# EVQ4242-VE-00B_schematic.net
KiCad netlist of a schematic drawn in Altium Designer
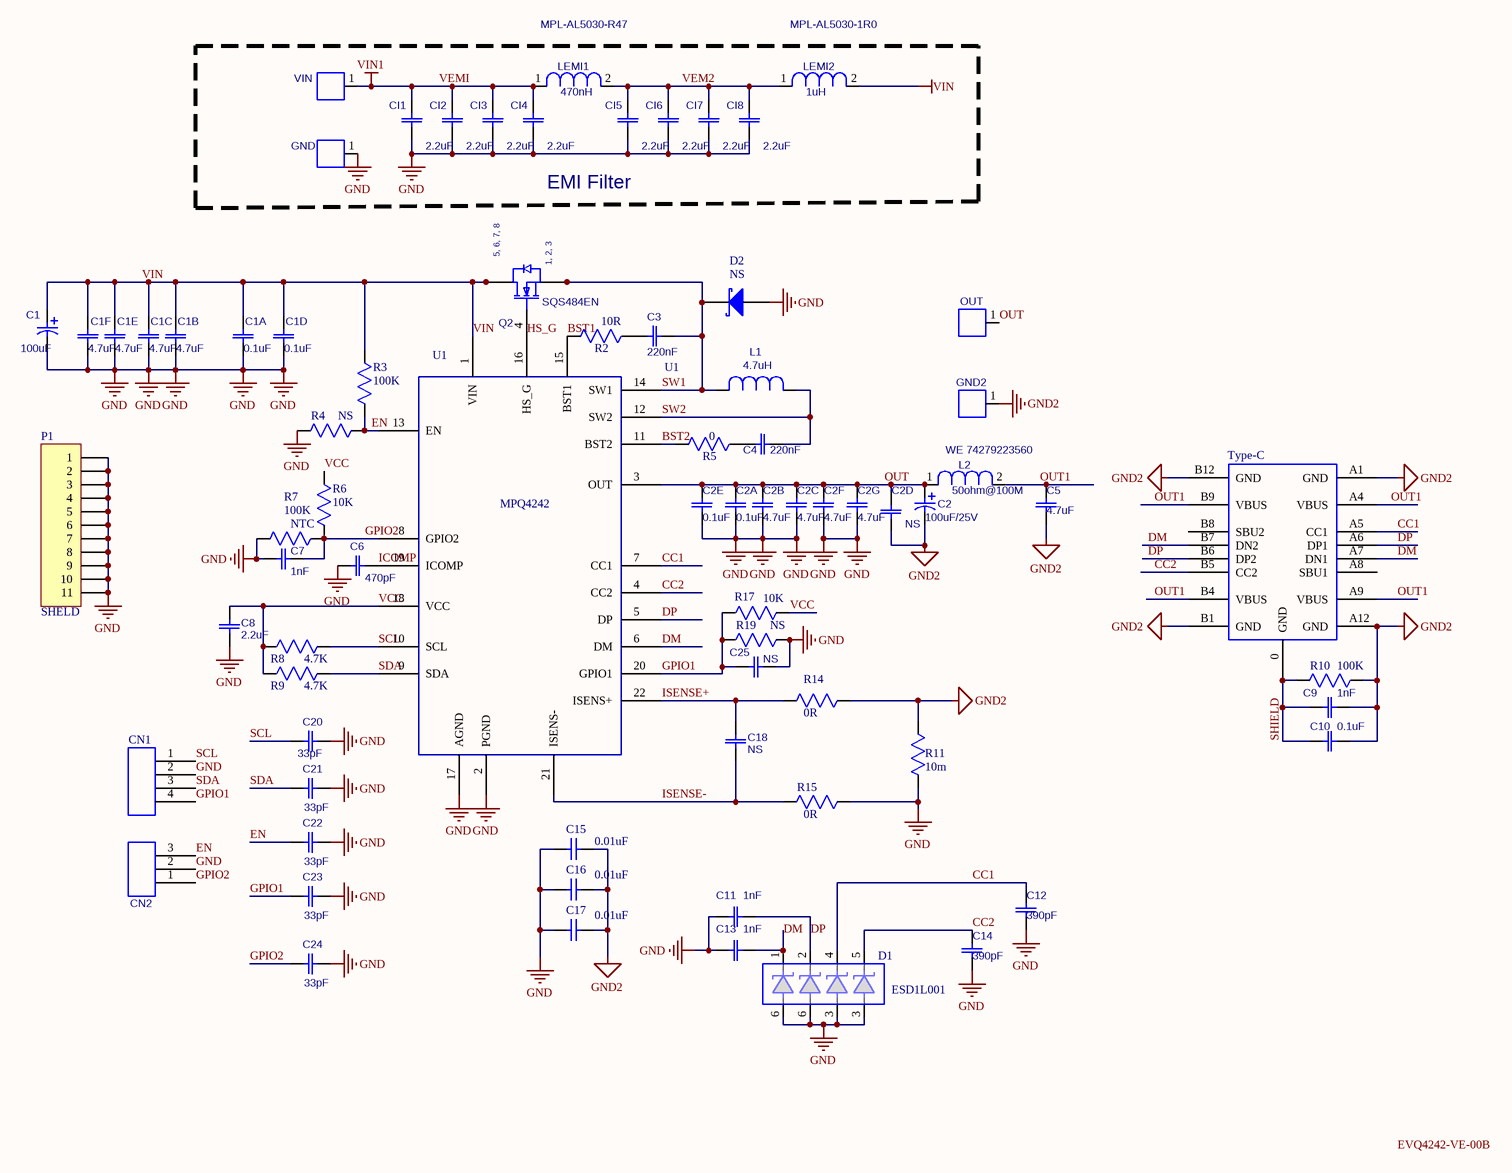
[diagram p0: EVQ4242-VE-00B_schematic.SchDoc]

(export (version "E")
  (design (tool "Eeschema 10.0.6"))
  (components
    (comp (ref "C1")
      (value "100uF")
      (footprint "CAP/ELECT/SMD/C6")
      (description "Electrolytic Capacitor;50V;Electrolytic;DIP")
      (fields (field (name "MANUFACTURER") "{Manufacturer}") (field (name "PART NUMBER") "07.0271"))
      (libsource (lib "MPSLab") (part "CAP/ELECT/DIP/OD5.3P2.0"))
    )
    (comp (ref "C1A")
      (value "0.1uF")
      (footprint "CAP/0402")
      (description "{Description}")
      (fields (field (name "MANUFACTURER") "{Manufacturer}"))
      (libsource (lib "*") (part "CAP0603"))
    )
    (comp (ref "C1B")
      (value "4.7uF")
      (footprint "CAP/0805")
      (description "{Description}")
      (fields (field (name "MANUFACTURER") "{Manufacturer}"))
      (libsource (lib "*") (part "CAP0603"))
    )
    (comp (ref "C1C")
      (value "4.7uF")
      (footprint "CAP/0805")
      (description "Ceramic Cap., 50V, X7R")
      (fields (field (name "MANUFACTURER") "TDK"))
      (libsource (lib "*") (part "CAP1210"))
    )
    (comp (ref "C1D")
      (value "0.1uF")
      (footprint "CAP/0402")
      (description "{Description}")
      (fields (field (name "MANUFACTURER") "{Manufacturer}"))
      (libsource (lib "*") (part "CAP0603"))
    )
    (comp (ref "C1E")
      (value "4.7uF")
      (footprint "CAP/0805")
      (description "{Description}")
      (fields (field (name "MANUFACTURER") "{Manufacturer}"))
      (libsource (lib "*") (part "CAP0603"))
    )
    (comp (ref "C1F")
      (value "4.7uF")
      (footprint "CAP/0805")
      (description "Ceramic Cap., 50V, X7R")
      (fields (field (name "MANUFACTURER") "TDK"))
      (libsource (lib "*") (part "CAP1210"))
    )
    (comp (ref "C2")
      (value "100uF/25V")
      (footprint "6.6mm*6.6mm")
      (description "Electrolytic Capacitor;50V;Electrolytic;DIP")
      (fields (field (name "MANUFACTURER") "{Manufacturer}") (field (name "PART NUMBER") "07.0271"))
      (libsource (lib "MPSLab") (part "CAP/ELECT/DIP/OD5.3P2.0"))
    )
    (comp (ref "C2A")
      (value "0.1uF")
      (footprint "CAP/0402")
      (description "{Description}")
      (fields (field (name "MANUFACTURER") "{Manufacturer}"))
      (libsource (lib "*") (part "CAP0603"))
    )
    (comp (ref "C2B")
      (value "4.7uF")
      (footprint "CAP/0805")
      (description "{Description}")
      (fields (field (name "MANUFACTURER") "{Manufacturer}"))
      (libsource (lib "*") (part "CAP0603"))
    )
    (comp (ref "C2C")
      (value "4.7uF")
      (footprint "CAP/0805")
      (description "{Description}")
      (fields (field (name "MANUFACTURER") "{Manufacturer}"))
      (libsource (lib "*") (part "CAP0603"))
    )
    (comp (ref "C2D")
      (value "NS")
      (footprint "CAP/0805")
      (description "{Description}")
      (fields (field (name "MANUFACTURER") "{Manufacturer}"))
      (libsource (lib "*") (part "CAP0603"))
    )
    (comp (ref "C2E")
      (value "0.1uF")
      (footprint "CAP/0402")
      (description "{Description}")
      (fields (field (name "MANUFACTURER") "{Manufacturer}"))
      (libsource (lib "*") (part "CAP0603"))
    )
    (comp (ref "C2F")
      (value "4.7uF")
      (footprint "CAP/0805")
      (description "{Description}")
      (fields (field (name "MANUFACTURER") "{Manufacturer}"))
      (libsource (lib "*") (part "CAP0603"))
    )
    (comp (ref "C2G")
      (value "4.7uF")
      (footprint "CAP/0805")
      (description "{Description}")
      (fields (field (name "MANUFACTURER") "{Manufacturer}"))
      (libsource (lib "*") (part "CAP0603"))
    )
    (comp (ref "C3")
      (value "220nF")
      (footprint "CAP/0402")
      (description "{Description}")
      (fields (field (name "MANUFACTURER") "{Manufacturer}"))
      (libsource (lib "*") (part "CAP0603"))
    )
    (comp (ref "C4")
      (value "220nF")
      (footprint "CAP/0402")
      (description "{Description}")
      (fields (field (name "MANUFACTURER") "{Manufacturer}"))
      (libsource (lib "*") (part "CAP0603"))
    )
    (comp (ref "C5")
      (value "4.7uF")
      (footprint "CAP/0603")
      (description "{Description}")
      (fields (field (name "MANUFACTURER") "{Manufacturer}"))
      (libsource (lib "*") (part "CAP0603"))
    )
    (comp (ref "C6")
      (value "470pF")
      (footprint "CAP/0402")
      (description "{Description}")
      (fields (field (name "MANUFACTURER") "{Manufacturer}"))
      (libsource (lib "*") (part "CAP0603"))
    )
    (comp (ref "C7")
      (value "1nF")
      (footprint "CAP/0603")
      (description "{Description}")
      (fields (field (name "MANUFACTURER") "{Manufacturer}"))
      (libsource (lib "*") (part "CAP0603"))
    )
    (comp (ref "C8")
      (value "2.2uF")
      (footprint "CAP/0402")
      (description "{Description}")
      (fields (field (name "MANUFACTURER") "{Manufacturer}"))
      (libsource (lib "*") (part "CAP0603"))
    )
    (comp (ref "C9")
      (value "1nF")
      (footprint "CAP/0603")
      (description "Ceramic Cap.,50V,X7R")
      (fields (field (name "MANUFACTURER") "WE") (field (name "Comment") "CA~{P}0603"))
      (libsource (lib "*") (part "CAP0603"))
    )
    (comp (ref "C10")
      (value "0.1uF")
      (footprint "CAP/0603")
      (description "Ceramic Cap.,50V,X7R")
      (fields (field (name "MANUFACTURER") "WE") (field (name "Comment") "CA~{P}0603"))
      (libsource (lib "*") (part "CAP0603"))
    )
    (comp (ref "C11")
      (value "1nF")
      (footprint "CAP/0402")
      (description "Ceramic Cap.,50V,C0G")
      (fields (field (name "MANUFACTURER") "Murata") (field (name "Comment") "CA~{P}0603"))
      (libsource (lib "*") (part "CAP0603"))
    )
    (comp (ref "C12")
      (value "390pF")
      (footprint "CAP/0402")
      (description "{Description}")
      (fields (field (name "MANUFACTURER") "{Manufacturer}"))
      (libsource (lib "*") (part "CAP0603"))
    )
    (comp (ref "C13")
      (value "1nF")
      (footprint "CAP/0402")
      (description "Ceramic Cap.,50V,C0G")
      (fields (field (name "MANUFACTURER") "Murata") (field (name "Comment") "CA~{P}0603"))
      (libsource (lib "*") (part "CAP0603"))
    )
    (comp (ref "C14")
      (value "390pF")
      (footprint "CAP/0402")
      (description "{Description}")
      (fields (field (name "MANUFACTURER") "{Manufacturer}"))
      (libsource (lib "*") (part "CAP0603"))
    )
    (comp (ref "C15")
      (value "0.01uF")
      (footprint "CAP/0402")
      (description "Capacitor")
      (fields (field (name "MANUFACTURER") "muRata") (field (name "Comment") "Cap"))
      (libsource (lib "SMCAP") (part "Cap"))
    )
    (comp (ref "C16")
      (value "0.01uF")
      (footprint "CAP/0402")
      (description "Capacitor")
      (fields (field (name "MANUFACTURER") "muRata") (field (name "Comment") "Cap"))
      (libsource (lib "SMCAP") (part "Cap"))
    )
    (comp (ref "C17")
      (value "0.01uF")
      (footprint "CAP/0402")
      (description "Capacitor")
      (fields (field (name "MANUFACTURER") "muRata") (field (name "Comment") "Cap"))
      (libsource (lib "SMCAP") (part "Cap"))
    )
    (comp (ref "C18")
      (value "NS")
      (footprint "CAP/0402")
      (description "{Description}")
      (fields (field (name "MANUFACTURER") "{Manufacturer}"))
      (libsource (lib "*") (part "CAP0603"))
    )
    (comp (ref "C20")
      (value "33pF")
      (footprint "CAP0603")
      (description "{Description}")
      (fields (field (name "MANUFACTURER") "{Manufacturer}"))
      (libsource (lib "MPS_CAPACITOR") (part "CAP0402"))
    )
    (comp (ref "C21")
      (value "33pF")
      (footprint "CAP0603")
      (description "{Description}")
      (fields (field (name "MANUFACTURER") "{Manufacturer}"))
      (libsource (lib "MPS_CAPACITOR") (part "CAP0402"))
    )
    (comp (ref "C22")
      (value "33pF")
      (footprint "CAP0603")
      (description "{Description}")
      (fields (field (name "MANUFACTURER") "{Manufacturer}"))
      (libsource (lib "MPS_CAPACITOR") (part "CAP0402"))
    )
    (comp (ref "C23")
      (value "33pF")
      (footprint "CAP0603")
      (description "{Description}")
      (fields (field (name "MANUFACTURER") "{Manufacturer}"))
      (libsource (lib "MPS_CAPACITOR") (part "CAP0402"))
    )
    (comp (ref "C24")
      (value "33pF")
      (footprint "CAP0603")
      (description "{Description}")
      (fields (field (name "MANUFACTURER") "{Manufacturer}"))
      (libsource (lib "MPS_CAPACITOR") (part "CAP0402"))
    )
    (comp (ref "C25")
      (value "NS")
      (footprint "CAP/0603")
      (description "{Description}")
      (fields (field (name "MANUFACTURER") "{Manufacturer}"))
      (libsource (lib "*") (part "CAP0603"))
    )
    (comp (ref "CI1")
      (value "2.2uF")
      (footprint "CAP0603")
      (description "{Description}")
      (fields (field (name "MANUFACTURER") "{Manufacturer}") (field (name "Comment") "CAP0603"))
      (libsource (lib "MPS_CAPACITOR") (part "CAP0603"))
    )
    (comp (ref "CI2")
      (value "2.2uF")
      (footprint "CAP0603")
      (description "{Description}")
      (fields (field (name "MANUFACTURER") "{Manufacturer}") (field (name "Comment") "CAP0603"))
      (libsource (lib "MPS_CAPACITOR") (part "CAP0603"))
    )
    (comp (ref "CI3")
      (value "2.2uF")
      (footprint "CAP0603")
      (description "{Description}")
      (fields (field (name "MANUFACTURER") "{Manufacturer}") (field (name "Comment") "CAP0603"))
      (libsource (lib "MPS_CAPACITOR") (part "CAP0603"))
    )
    (comp (ref "CI4")
      (value "2.2uF")
      (footprint "CAP0603")
      (description "{Description}")
      (fields (field (name "MANUFACTURER") "{Manufacturer}") (field (name "Comment") "CAP0603"))
      (libsource (lib "MPS_CAPACITOR") (part "CAP0603"))
    )
    (comp (ref "CI5")
      (value "2.2uF")
      (footprint "CAP0603")
      (description "{Description}")
      (fields (field (name "MANUFACTURER") "{Manufacturer}") (field (name "Comment") "CAP0603"))
      (libsource (lib "MPS_CAPACITOR") (part "CAP0603"))
    )
    (comp (ref "CI6")
      (value "2.2uF")
      (footprint "CAP0603")
      (description "{Description}")
      (fields (field (name "MANUFACTURER") "{Manufacturer}") (field (name "Comment") "CAP0603"))
      (libsource (lib "MPS_CAPACITOR") (part "CAP0603"))
    )
    (comp (ref "CI7")
      (value "2.2uF")
      (footprint "CAP0603")
      (description "{Description}")
      (fields (field (name "MANUFACTURER") "{Manufacturer}") (field (name "Comment") "CAP0603"))
      (libsource (lib "MPS_CAPACITOR") (part "CAP0603"))
    )
    (comp (ref "CI8")
      (value "2.2uF")
      (footprint "CAP0603")
      (description "{Description}")
      (fields (field (name "MANUFACTURER") "{Manufacturer}") (field (name "Comment") "CAP0603"))
      (libsource (lib "MPS_CAPACITOR") (part "CAP0603"))
    )
    (comp (ref "CN1")
      (value "HEADER 4")
      (footprint "HEADER 1X4")
      (libsource (lib "T-EV5101-VE-00A") (part "HEADER 4"))
    )
    (comp (ref "CN2") (value "AC") (footprint "CONN/3PIN/2.54MM") (libsource (lib "Connector") (part "AC")))
    (comp (ref "D1")
      (value "ESD1L001")
      (footprint "ESD0001")
      (description "ESD Diode")
      (fields (field (name "MANUFACTURER") "Onsemi"))
      (libsource (lib "T-EVQ5031-4272-RE-00A") (part "ESD1L001"))
    )
    (comp (ref "D2")
      (value "NS")
      (footprint "SOD123")
      (description "Schottky Diode")
      (libsource (lib "Development kit-5M1270ZT144C5_1") (part "D Schottky"))
    )
    (comp (ref "GND")
      (value "CONN/1MM")
      (footprint "TP/2MM")
      (description "{Description}")
      (libsource (lib "Connector") (part "CONN/2MM"))
    )
    (comp (ref "GND2")
      (value "CONN/TP")
      (footprint "TP/2MM")
      (description "{Description}")
      (fields (field (name "MANUFACTURER") "{Manufacturer}"))
      (libsource (lib "Connector") (part "CONN/TP"))
    )
    (comp (ref "L1")
      (value "4.7uH")
      (footprint "7443551470")
      (description "{Description}")
      (fields (field (name "MANUFACTURER") "{Manufacturer}"))
      (libsource (lib "*") (part "TOKO106C"))
    )
    (comp (ref "L2")
      (value "50ohm@100M")
      (footprint "sm1206")
      (description "{Description}")
      (fields
        (field (name "PACKAGE") "WE 74279223560")
        (field (name "MANUFACTURER") "{Manufacturer}")
        (field (name "Comment") "L-10X10")
      )
      (libsource (lib "Inductor") (part "L-10X10"))
    )
    (comp (ref "LEMI1")
      (value "470nH")
      (footprint "L5030")
      (description "Inductor, 1.45A, D62LCB")
      (fields
        (field (name "PACKAGE") "MPL-AL5030-R47")
        (field (name "MANUFACTURER") "Toko")
        (field (name "Comment") "TDK-2520")
      )
      (libsource (lib "MPS_INDUCTOR") (part "TDK-2520"))
    )
    (comp (ref "LEMI2")
      (value "1uH")
      (footprint "L5030")
      (description "Inductor, 1.45A, D62LCB")
      (fields
        (field (name "MANUFACTURER") "Toko")
        (field (name "MANUFACTURER P/N") "MPL-AL5030-1R0")
        (field (name "Comment") "TDK-2520")
      )
      (libsource (lib "MPS_INDUCTOR") (part "TDK-2520"))
    )
    (comp (ref "OUT")
      (value "CONN/TP")
      (footprint "TP/2MM")
      (description "{Description}")
      (fields (field (name "MANUFACTURER") "{Manufacturer}"))
      (libsource (lib "Connector") (part "CONN/TP"))
    )
    (comp (ref "P1")
      (value "SHELD")
      (footprint "sheld")
      (libsource (lib "T-EVQ4242-VE-00A_1") (part "SHELD"))
    )
    (comp (ref "Q2")
      (value "SQS484EN")
      (footprint "SQS484EN")
      (description "AM4392N")
      (fields (field (name "ALTIUM_VALUE") "U1"))
      (libsource (lib "MOSFET") (part "AM4392N"))
    )
    (comp (ref "R2")
      (value "10R")
      (footprint "RES0402")
      (fields (field (name "Comment") "RES/DIP/1/2W"))
      (libsource (lib "Resistor") (part "RES/DIP/1/2W"))
    )
    (comp (ref "R3")
      (value "100K")
      (footprint "RES0603")
      (fields (field (name "Comment") "RES/DIP/1/2W"))
      (libsource (lib "Resistor") (part "RES/DIP/1/2W"))
    )
    (comp (ref "R4")
      (value "NS")
      (footprint "RES0603")
      (fields (field (name "Comment") "RES/DIP/1/2W"))
      (libsource (lib "Resistor") (part "RES/DIP/1/2W"))
    )
    (comp (ref "R5")
      (value "0")
      (footprint "RES0402")
      (fields (field (name "Comment") "RES/DIP/1/2W"))
      (libsource (lib "Resistor") (part "RES/DIP/1/2W"))
    )
    (comp (ref "R6")
      (value "10K")
      (footprint "RES0603")
      (fields (field (name "Comment") "RES/DIP/1/2W"))
      (libsource (lib "Resistor") (part "RES/DIP/1/2W"))
    )
    (comp (ref "R7")
      (value "NTC")
      (footprint "RES0603")
      (fields (field (name "ALTIUM_UNNAMED_1") "100K") (field (name "Comment") "RES/DIP/1/2W"))
      (libsource (lib "Resistor") (part "RES/DIP/1/2W"))
    )
    (comp (ref "R8")
      (value "4.7K")
      (footprint "RES0603")
      (fields (field (name "Comment") "RES/DIP/1/2W"))
      (libsource (lib "Resistor") (part "RES/DIP/1/2W"))
    )
    (comp (ref "R9")
      (value "4.7K")
      (footprint "RES0603")
      (fields (field (name "Comment") "RES/DIP/1/2W"))
      (libsource (lib "Resistor") (part "RES/DIP/1/2W"))
    )
    (comp (ref "R10")
      (value "100K")
      (footprint "RES0603")
      (fields (field (name "Comment") "RES/DIP/1/2W"))
      (libsource (lib "Resistor") (part "RES/DIP/1/2W"))
    )
    (comp (ref "R11")
      (value "10m")
      (footprint "l1508")
      (fields (field (name "Comment") "RES/DIP/1/2W"))
      (libsource (lib "Resistor") (part "RES/DIP/1/2W"))
    )
    (comp (ref "R14")
      (value "0R")
      (footprint "RES0402")
      (fields (field (name "Comment") "RES/DIP/1/2W"))
      (libsource (lib "Resistor") (part "RES/DIP/1/2W"))
    )
    (comp (ref "R15")
      (value "0R")
      (footprint "RES0402")
      (fields (field (name "Comment") "RES/DIP/1/2W"))
      (libsource (lib "Resistor") (part "RES/DIP/1/2W"))
    )
    (comp (ref "R17")
      (value "10K")
      (footprint "RES0603")
      (fields (field (name "Comment") "RES/DIP/1/2W"))
      (libsource (lib "Resistor") (part "RES/DIP/1/2W"))
    )
    (comp (ref "R19")
      (value "NS")
      (footprint "RES0603")
      (fields (field (name "Comment") "RES/DIP/1/2W"))
      (libsource (lib "Resistor") (part "RES/DIP/1/2W"))
    )
    (comp (ref "Type-C")
      (value "New Type_c")
      (footprint "New Type-C")
      (libsource (lib "BI-EVQ4252-QV-00A") (part "New Type_c"))
    )
    (comp (ref "U1")
      (value "MPQ4242")
      (footprint "QFN-22 (4mm×5mm)")
      (description "Buck-boost converter")
      (libsource (lib "T-EVQ4242-VE-00A") (part "QFN-22 (4MM*5MM)"))
    )
    (comp (ref "VIN")
      (value "CONN/2MM")
      (footprint "TP/2MM")
      (description "{Description}")
      (libsource (lib "Connector") (part "CONN/2MM"))
    )
  )
  (nets
    (net (code "1") (name "/BST1") (class "Default")
      (node (ref "R2") (pin "1") (pintype "passive"))
      (node (ref "U1") (pin "15") (pinfunction "BST1_15") (pintype "power_in"))
    )
    (net (code "2") (name "/BST2") (class "Default")
      (node (ref "R5") (pin "1") (pintype "passive"))
      (node (ref "U1") (pin "11") (pinfunction "BST2_11") (pintype "power_in"))
    )
    (net (code "3") (name "/CC1") (class "Default")
      (node (ref "C12") (pin "1") (pintype "passive"))
      (node (ref "D1") (pin "4") (pintype "passive"))
      (node (ref "Type-C") (pin "A5") (pinfunction "CC1_A5") (pintype "passive"))
      (node (ref "U1") (pin "7") (pinfunction "CC1_7") (pintype "power_in"))
    )
    (net (code "4") (name "/CC2") (class "Default")
      (node (ref "C14") (pin "1") (pintype "passive"))
      (node (ref "D1") (pin "5") (pintype "passive"))
      (node (ref "Type-C") (pin "B5") (pinfunction "CC2_B5") (pintype "passive"))
      (node (ref "U1") (pin "4") (pinfunction "CC2_4") (pintype "power_in"))
    )
    (net (code "5") (name "/DM") (class "Default")
      (node (ref "C13") (pin "2") (pintype "passive"))
      (node (ref "D1") (pin "1") (pintype "passive"))
      (node (ref "Type-C") (pin "A7") (pinfunction "DN1_A7") (pintype "passive"))
      (node (ref "Type-C") (pin "B7") (pinfunction "DN2_B7") (pintype "passive"))
      (node (ref "U1") (pin "6") (pinfunction "DM_6") (pintype "power_in"))
    )
    (net (code "6") (name "/DP") (class "Default")
      (node (ref "C11") (pin "2") (pintype "passive"))
      (node (ref "D1") (pin "2") (pintype "passive"))
      (node (ref "Type-C") (pin "A6") (pinfunction "DP1_A6") (pintype "passive"))
      (node (ref "Type-C") (pin "B6") (pinfunction "DP2_B6") (pintype "passive"))
      (node (ref "U1") (pin "5") (pinfunction "DP_5") (pintype "power_in"))
    )
    (net (code "7") (name "/EN") (class "Default")
      (node (ref "C22") (pin "2") (pintype "passive"))
      (node (ref "CN2") (pin "3") (pintype "passive"))
      (node (ref "R3") (pin "1") (pintype "passive"))
      (node (ref "R4") (pin "1") (pintype "passive"))
      (node (ref "U1") (pin "13") (pinfunction "EN_13") (pintype "power_in"))
    )
    (net (code "9") (name "/GPIO1") (class "Default")
      (node (ref "C23") (pin "2") (pintype "passive"))
      (node (ref "C25") (pin "1") (pintype "passive"))
      (node (ref "CN1") (pin "4") (pintype "passive"))
      (node (ref "R17") (pin "1") (pintype "passive"))
      (node (ref "R19") (pin "1") (pintype "passive"))
      (node (ref "U1") (pin "20") (pinfunction "GPIO1_20") (pintype "power_in"))
    )
    (net (code "10") (name "/GPIO2") (class "Default")
      (node (ref "C24") (pin "2") (pintype "passive"))
      (node (ref "C7") (pin "2") (pintype "passive"))
      (node (ref "CN2") (pin "1") (pintype "passive"))
      (node (ref "R6") (pin "1") (pintype "passive"))
      (node (ref "R7") (pin "1") (pintype "passive"))
      (node (ref "U1") (pin "8") (pinfunction "GPIO2_8") (pintype "power_in"))
    )
    (net (code "11") (name "/HS_G") (class "Default")
      (node (ref "Q2") (pin "4") (pinfunction "G_4") (pintype "passive"))
      (node (ref "U1") (pin "16") (pinfunction "HS_G_16") (pintype "power_in"))
    )
    (net (code "12") (name "/ICOMP") (class "Default")
      (node (ref "C6") (pin "2") (pintype "passive"))
      (node (ref "U1") (pin "19") (pinfunction "ICOMP_19") (pintype "power_in"))
    )
    (net (code "13") (name "/ISENSE+") (class "Default")
      (node (ref "C18") (pin "1") (pintype "passive"))
      (node (ref "R14") (pin "2") (pintype "passive"))
      (node (ref "U1") (pin "22") (pinfunction "ISENS+_22") (pintype "power_in"))
    )
    (net (code "14") (name "/ISENSE-") (class "Default")
      (node (ref "C18") (pin "2") (pintype "passive"))
      (node (ref "R15") (pin "1") (pintype "passive"))
      (node (ref "U1") (pin "21") (pinfunction "ISENS-_21") (pintype "power_in"))
    )
    (net (code "15") (name "/OUT") (class "Default")
      (node (ref "C2") (pin "1") (pintype "passive"))
      (node (ref "C2A") (pin "1") (pintype "passive"))
      (node (ref "C2B") (pin "1") (pintype "passive"))
      (node (ref "C2C") (pin "1") (pintype "passive"))
      (node (ref "C2D") (pin "1") (pintype "passive"))
      (node (ref "C2E") (pin "1") (pintype "passive"))
      (node (ref "C2F") (pin "1") (pintype "passive"))
      (node (ref "C2G") (pin "1") (pintype "passive"))
      (node (ref "L2") (pin "1") (pintype "passive"))
      (node (ref "OUT") (pin "1") (pintype "passive"))
      (node (ref "U1") (pin "3") (pinfunction "OUT_3") (pintype "power_in"))
    )
    (net (code "16") (name "/OUT1") (class "Default")
      (node (ref "C5") (pin "1") (pintype "passive"))
      (node (ref "L2") (pin "2") (pintype "passive"))
      (node (ref "Type-C") (pin "A4") (pinfunction "VBUS_A4") (pintype "passive"))
      (node (ref "Type-C") (pin "A9") (pinfunction "VBUS_A9") (pintype "passive"))
      (node (ref "Type-C") (pin "B4") (pinfunction "VBUS_B4") (pintype "passive"))
      (node (ref "Type-C") (pin "B9") (pinfunction "VBUS_B9") (pintype "passive"))
    )
    (net (code "17") (name "/SCL") (class "Default")
      (node (ref "C20") (pin "2") (pintype "passive"))
      (node (ref "CN1") (pin "1") (pintype "passive"))
      (node (ref "R8") (pin "2") (pintype "passive"))
      (node (ref "U1") (pin "10") (pinfunction "SCL_10") (pintype "power_in"))
    )
    (net (code "18") (name "/SDA") (class "Default")
      (node (ref "C21") (pin "2") (pintype "passive"))
      (node (ref "CN1") (pin "3") (pintype "passive"))
      (node (ref "R9") (pin "2") (pintype "passive"))
      (node (ref "U1") (pin "9") (pinfunction "SDA_9") (pintype "power_in"))
    )
    (net (code "19") (name "/SHIELD") (class "Default")
      (node (ref "C10") (pin "1") (pintype "passive"))
      (node (ref "C9") (pin "1") (pintype "passive"))
      (node (ref "R10") (pin "1") (pintype "passive"))
      (node (ref "Type-C") (pin "0") (pinfunction "GND_0") (pintype "passive"))
    )
    (net (code "20") (name "/SW1") (class "Default")
      (node (ref "C3") (pin "1") (pintype "passive"))
      (node (ref "D2") (pin "2") (pinfunction "K_2") (pintype "passive"))
      (node (ref "L1") (pin "1") (pintype "passive"))
      (node (ref "Q2") (pin "1") (pinfunction "S_1") (pintype "passive"))
      (node (ref "Q2") (pin "2") (pinfunction "S_2") (pintype "passive"))
      (node (ref "Q2") (pin "3") (pinfunction "S_3") (pintype "passive"))
      (node (ref "U1") (pin "14") (pinfunction "SW1_14") (pintype "power_in"))
    )
    (net (code "21") (name "/SW2") (class "Default")
      (node (ref "C4") (pin "1") (pintype "passive"))
      (node (ref "L1") (pin "2") (pintype "passive"))
      (node (ref "U1") (pin "12") (pinfunction "SW2_12") (pintype "power_in"))
    )
    (net (code "22") (name "/VCC") (class "Default")
      (node (ref "C8") (pin "1") (pintype "passive"))
      (node (ref "R17") (pin "2") (pintype "passive"))
      (node (ref "R6") (pin "2") (pintype "passive"))
      (node (ref "R8") (pin "1") (pintype "passive"))
      (node (ref "R9") (pin "1") (pintype "passive"))
      (node (ref "U1") (pin "18") (pinfunction "VCC_18") (pintype "power_in"))
    )
    (net (code "23") (name "/VEM2") (class "Default")
      (node (ref "CI5") (pin "2") (pintype "passive"))
      (node (ref "CI6") (pin "2") (pintype "passive"))
      (node (ref "CI7") (pin "2") (pintype "passive"))
      (node (ref "CI8") (pin "2") (pintype "passive"))
      (node (ref "LEMI1") (pin "2") (pintype "passive"))
      (node (ref "LEMI2") (pin "1") (pintype "passive"))
    )
    (net (code "24") (name "GND") (class "Default")
      (node (ref "C1") (pin "2") (pintype "passive"))
      (node (ref "C11") (pin "1") (pintype "passive"))
      (node (ref "C12") (pin "2") (pintype "passive"))
      (node (ref "C13") (pin "1") (pintype "passive"))
      (node (ref "C14") (pin "2") (pintype "passive"))
      (node (ref "C15") (pin "1") (pinfunction "1_1") (pintype "passive"))
      (node (ref "C16") (pin "1") (pinfunction "1_1") (pintype "passive"))
      (node (ref "C17") (pin "1") (pinfunction "1_1") (pintype "passive"))
      (node (ref "C1A") (pin "1") (pintype "passive"))
      (node (ref "C1B") (pin "1") (pintype "passive"))
      (node (ref "C1C") (pin "1") (pintype "passive"))
      (node (ref "C1D") (pin "1") (pintype "passive"))
      (node (ref "C1E") (pin "1") (pintype "passive"))
      (node (ref "C1F") (pin "1") (pintype "passive"))
      (node (ref "C20") (pin "1") (pintype "passive"))
      (node (ref "C21") (pin "1") (pintype "passive"))
      (node (ref "C22") (pin "1") (pintype "passive"))
      (node (ref "C23") (pin "1") (pintype "passive"))
      (node (ref "C24") (pin "1") (pintype "passive"))
      (node (ref "C25") (pin "2") (pintype "passive"))
      (node (ref "C2A") (pin "2") (pintype "passive"))
      (node (ref "C2B") (pin "2") (pintype "passive"))
      (node (ref "C2C") (pin "2") (pintype "passive"))
      (node (ref "C2E") (pin "2") (pintype "passive"))
      (node (ref "C2F") (pin "2") (pintype "passive"))
      (node (ref "C2G") (pin "2") (pintype "passive"))
      (node (ref "C6") (pin "1") (pintype "passive"))
      (node (ref "C7") (pin "1") (pintype "passive"))
      (node (ref "C8") (pin "2") (pintype "passive"))
      (node (ref "CI1") (pin "1") (pintype "passive"))
      (node (ref "CI2") (pin "1") (pintype "passive"))
      (node (ref "CI3") (pin "1") (pintype "passive"))
      (node (ref "CI4") (pin "1") (pintype "passive"))
      (node (ref "CI5") (pin "1") (pintype "passive"))
      (node (ref "CI6") (pin "1") (pintype "passive"))
      (node (ref "CI7") (pin "1") (pintype "passive"))
      (node (ref "CI8") (pin "1") (pintype "passive"))
      (node (ref "CN1") (pin "2") (pintype "passive"))
      (node (ref "CN2") (pin "2") (pintype "passive"))
      (node (ref "D1") (pin "3") (pintype "passive"))
      (node (ref "D1") (pin "6") (pintype "passive"))
      (node (ref "D2") (pin "1") (pinfunction "A_1") (pintype "passive"))
      (node (ref "GND") (pin "1") (pintype "passive"))
      (node (ref "P1") (pin "1") (pinfunction "1_1") (pintype "passive"))
      (node (ref "P1") (pin "10") (pinfunction "10_10") (pintype "passive"))
      (node (ref "P1") (pin "11") (pinfunction "11_11") (pintype "passive"))
      (node (ref "P1") (pin "2") (pinfunction "2_2") (pintype "passive"))
      (node (ref "P1") (pin "3") (pinfunction "3_3") (pintype "passive"))
      (node (ref "P1") (pin "4") (pinfunction "4_4") (pintype "passive"))
      (node (ref "P1") (pin "5") (pinfunction "5_5") (pintype "passive"))
      (node (ref "P1") (pin "6") (pinfunction "6_6") (pintype "passive"))
      (node (ref "P1") (pin "7") (pinfunction "7_7") (pintype "passive"))
      (node (ref "P1") (pin "8") (pinfunction "8_8") (pintype "passive"))
      (node (ref "P1") (pin "9") (pinfunction "9_9") (pintype "passive"))
      (node (ref "R11") (pin "1") (pintype "passive"))
      (node (ref "R15") (pin "2") (pintype "passive"))
      (node (ref "R19") (pin "2") (pintype "passive"))
      (node (ref "R4") (pin "2") (pintype "passive"))
      (node (ref "R7") (pin "2") (pintype "passive"))
      (node (ref "U1") (pin "17") (pinfunction "AGND_17") (pintype "power_in"))
      (node (ref "U1") (pin "2") (pinfunction "PGND_2") (pintype "power_in"))
    )
    (net (code "25") (name "GND2") (class "Default")
      (node (ref "C10") (pin "2") (pintype "passive"))
      (node (ref "C15") (pin "2") (pinfunction "2_2") (pintype "passive"))
      (node (ref "C16") (pin "2") (pinfunction "2_2") (pintype "passive"))
      (node (ref "C17") (pin "2") (pinfunction "2_2") (pintype "passive"))
      (node (ref "C2") (pin "2") (pintype "passive"))
      (node (ref "C2D") (pin "2") (pintype "passive"))
      (node (ref "C5") (pin "2") (pintype "passive"))
      (node (ref "C9") (pin "2") (pintype "passive"))
      (node (ref "GND2") (pin "1") (pintype "passive"))
      (node (ref "R10") (pin "2") (pintype "passive"))
      (node (ref "R11") (pin "2") (pintype "passive"))
      (node (ref "R14") (pin "1") (pintype "passive"))
      (node (ref "Type-C") (pin "A1") (pinfunction "GND_A1") (pintype "passive"))
      (node (ref "Type-C") (pin "A12") (pinfunction "GND_A12") (pintype "passive"))
      (node (ref "Type-C") (pin "B1") (pinfunction "GND_B1") (pintype "passive"))
      (node (ref "Type-C") (pin "B12") (pinfunction "GND_B12") (pintype "passive"))
    )
    (net (code "26") (name "Net-(C3-Pad2)") (class "Default")
      (node (ref "C3") (pin "2") (pintype "passive"))
      (node (ref "R2") (pin "2") (pintype "passive"))
    )
    (net (code "27") (name "Net-(C4-Pad2)") (class "Default")
      (node (ref "C4") (pin "2") (pintype "passive"))
      (node (ref "R5") (pin "2") (pintype "passive"))
    )
    (net (code "28") (name "VIN") (class "Default")
      (node (ref "C1") (pin "1") (pintype "passive"))
      (node (ref "C1A") (pin "2") (pintype "passive"))
      (node (ref "C1B") (pin "2") (pintype "passive"))
      (node (ref "C1C") (pin "2") (pintype "passive"))
      (node (ref "C1D") (pin "2") (pintype "passive"))
      (node (ref "C1E") (pin "2") (pintype "passive"))
      (node (ref "C1F") (pin "2") (pintype "passive"))
      (node (ref "LEMI2") (pin "2") (pintype "passive"))
      (node (ref "Q2") (pin "5") (pinfunction "D_5") (pintype "passive"))
      (node (ref "Q2") (pin "6") (pinfunction "D_6") (pintype "passive"))
      (node (ref "Q2") (pin "7") (pinfunction "D_7") (pintype "passive"))
      (node (ref "Q2") (pin "8") (pinfunction "D_8") (pintype "passive"))
      (node (ref "R3") (pin "2") (pintype "passive"))
      (node (ref "U1") (pin "1") (pinfunction "VIN_1") (pintype "power_in"))
    )
    (net (code "29") (name "VIN1") (class "Default")
      (node (ref "CI1") (pin "2") (pintype "passive"))
      (node (ref "CI2") (pin "2") (pintype "passive"))
      (node (ref "CI3") (pin "2") (pintype "passive"))
      (node (ref "CI4") (pin "2") (pintype "passive"))
      (node (ref "LEMI1") (pin "1") (pintype "passive"))
      (node (ref "VIN") (pin "1") (pintype "passive"))
    )
    (net (code "30") (name "unconnected-(CN2-Pad4)") (class "Default")
      (node (ref "CN2") (pin "4") (pintype "passive"))
    )
    (net (code "31") (name "unconnected-(CN2-Pad5)") (class "Default")
      (node (ref "CN2") (pin "5") (pintype "passive"))
    )
    (net (code "32") (name "unconnected-(Type-C-SBU1-PadA8)") (class "Default")
      (node (ref "Type-C") (pin "A8") (pinfunction "SBU1_A8") (pintype "passive"))
    )
    (net (code "33") (name "unconnected-(Type-C-SBU2-PadB8)") (class "Default")
      (node (ref "Type-C") (pin "B8") (pinfunction "SBU2_B8") (pintype "passive"))
    )
  )
)
